# converter.net
KiCad netlist of a schematic drawn in EAGLE
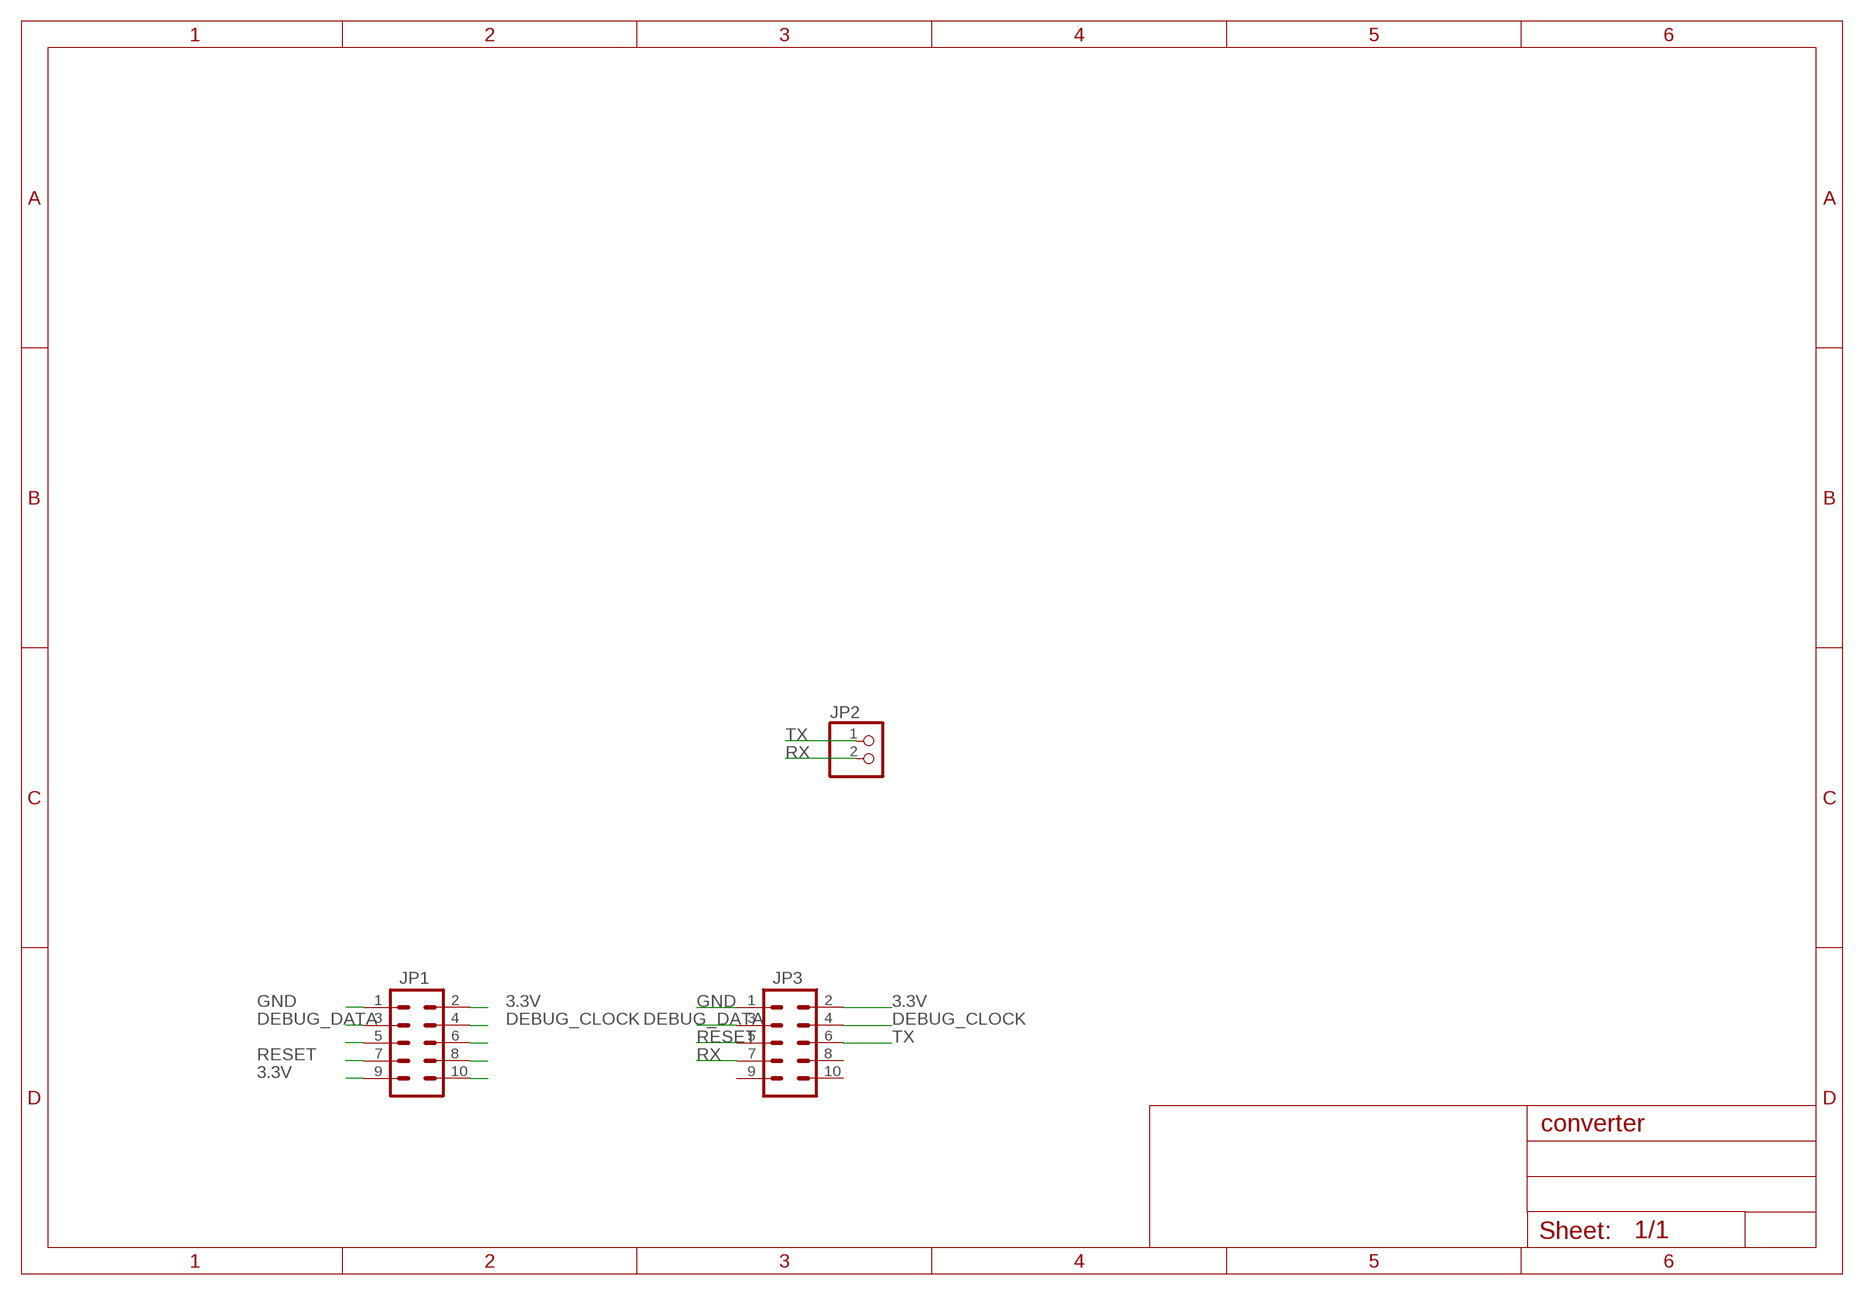
[diagram p0: schematic, sheet 1]

(export (version "E")
  (design (tool "Eeschema 10.0.6"))
  (components
    (comp (ref "JP1")
      (value "M05X2SHD")
      (footprint "eagle-import:2X5-SHROUDED")
      (libsource (lib "eagle-import") (part "M05X2SHD"))
    )
    (comp (ref "JP2")
      (value "PINHD-1X2")
      (footprint "eagle-import:1X02")
      (libsource (lib "eagle-import") (part "PINHD-1X2"))
    )
    (comp (ref "JP3")
      (value "M05X2SHD")
      (footprint "eagle-import:2X5-SHROUDED")
      (libsource (lib "eagle-import") (part "M05X2SHD"))
    )
  )
  (nets
    (net (code "1") (name "/3.3V") (class "Default")
      (node (ref "JP1") (pin "2") (pinfunction "2_2") (pintype "passive"))
      (node (ref "JP1") (pin "9") (pinfunction "9_9") (pintype "passive"))
      (node (ref "JP3") (pin "2") (pinfunction "2_2") (pintype "passive"))
    )
    (net (code "2") (name "/DEBUG_CLOCK") (class "Default")
      (node (ref "JP1") (pin "4") (pinfunction "4_4") (pintype "passive"))
      (node (ref "JP3") (pin "4") (pinfunction "4_4") (pintype "passive"))
    )
    (net (code "3") (name "/DEBUG_DATA") (class "Default")
      (node (ref "JP1") (pin "3") (pinfunction "3_3") (pintype "passive"))
      (node (ref "JP3") (pin "3") (pinfunction "3_3") (pintype "passive"))
    )
    (net (code "4") (name "/GND") (class "Default")
      (node (ref "JP1") (pin "1") (pinfunction "1_1") (pintype "passive"))
      (node (ref "JP3") (pin "1") (pinfunction "1_1") (pintype "passive"))
    )
    (net (code "5") (name "/RESET") (class "Default")
      (node (ref "JP1") (pin "7") (pinfunction "7_7") (pintype "passive"))
      (node (ref "JP3") (pin "5") (pinfunction "5_5") (pintype "passive"))
    )
    (net (code "6") (name "/RX") (class "Default")
      (node (ref "JP2") (pin "2") (pinfunction "2_2") (pintype "passive"))
      (node (ref "JP3") (pin "7") (pinfunction "7_7") (pintype "passive"))
    )
    (net (code "7") (name "/TX") (class "Default")
      (node (ref "JP2") (pin "1") (pinfunction "1_1") (pintype "passive"))
      (node (ref "JP3") (pin "6") (pinfunction "6_6") (pintype "passive"))
    )
    (net (code "8") (name "unconnected-(JP1-Pad5)") (class "Default")
      (node (ref "JP1") (pin "5") (pinfunction "5_5") (pintype "passive"))
    )
    (net (code "9") (name "unconnected-(JP1-Pad6)") (class "Default")
      (node (ref "JP1") (pin "6") (pinfunction "6_6") (pintype "passive"))
    )
    (net (code "10") (name "unconnected-(JP1-Pad8)") (class "Default")
      (node (ref "JP1") (pin "8") (pinfunction "8_8") (pintype "passive"))
    )
    (net (code "11") (name "unconnected-(JP1-Pad10)") (class "Default")
      (node (ref "JP1") (pin "10") (pinfunction "10_10") (pintype "passive"))
    )
    (net (code "12") (name "unconnected-(JP3-Pad8)") (class "Default")
      (node (ref "JP3") (pin "8") (pinfunction "8_8") (pintype "passive"))
    )
    (net (code "13") (name "unconnected-(JP3-Pad9)") (class "Default")
      (node (ref "JP3") (pin "9") (pinfunction "9_9") (pintype "passive"))
    )
    (net (code "14") (name "unconnected-(JP3-Pad10)") (class "Default")
      (node (ref "JP3") (pin "10") (pinfunction "10_10") (pintype "passive"))
    )
  )
)
